# KDP.net
KiCad netlist of a schematic drawn in EasyEDA Pro
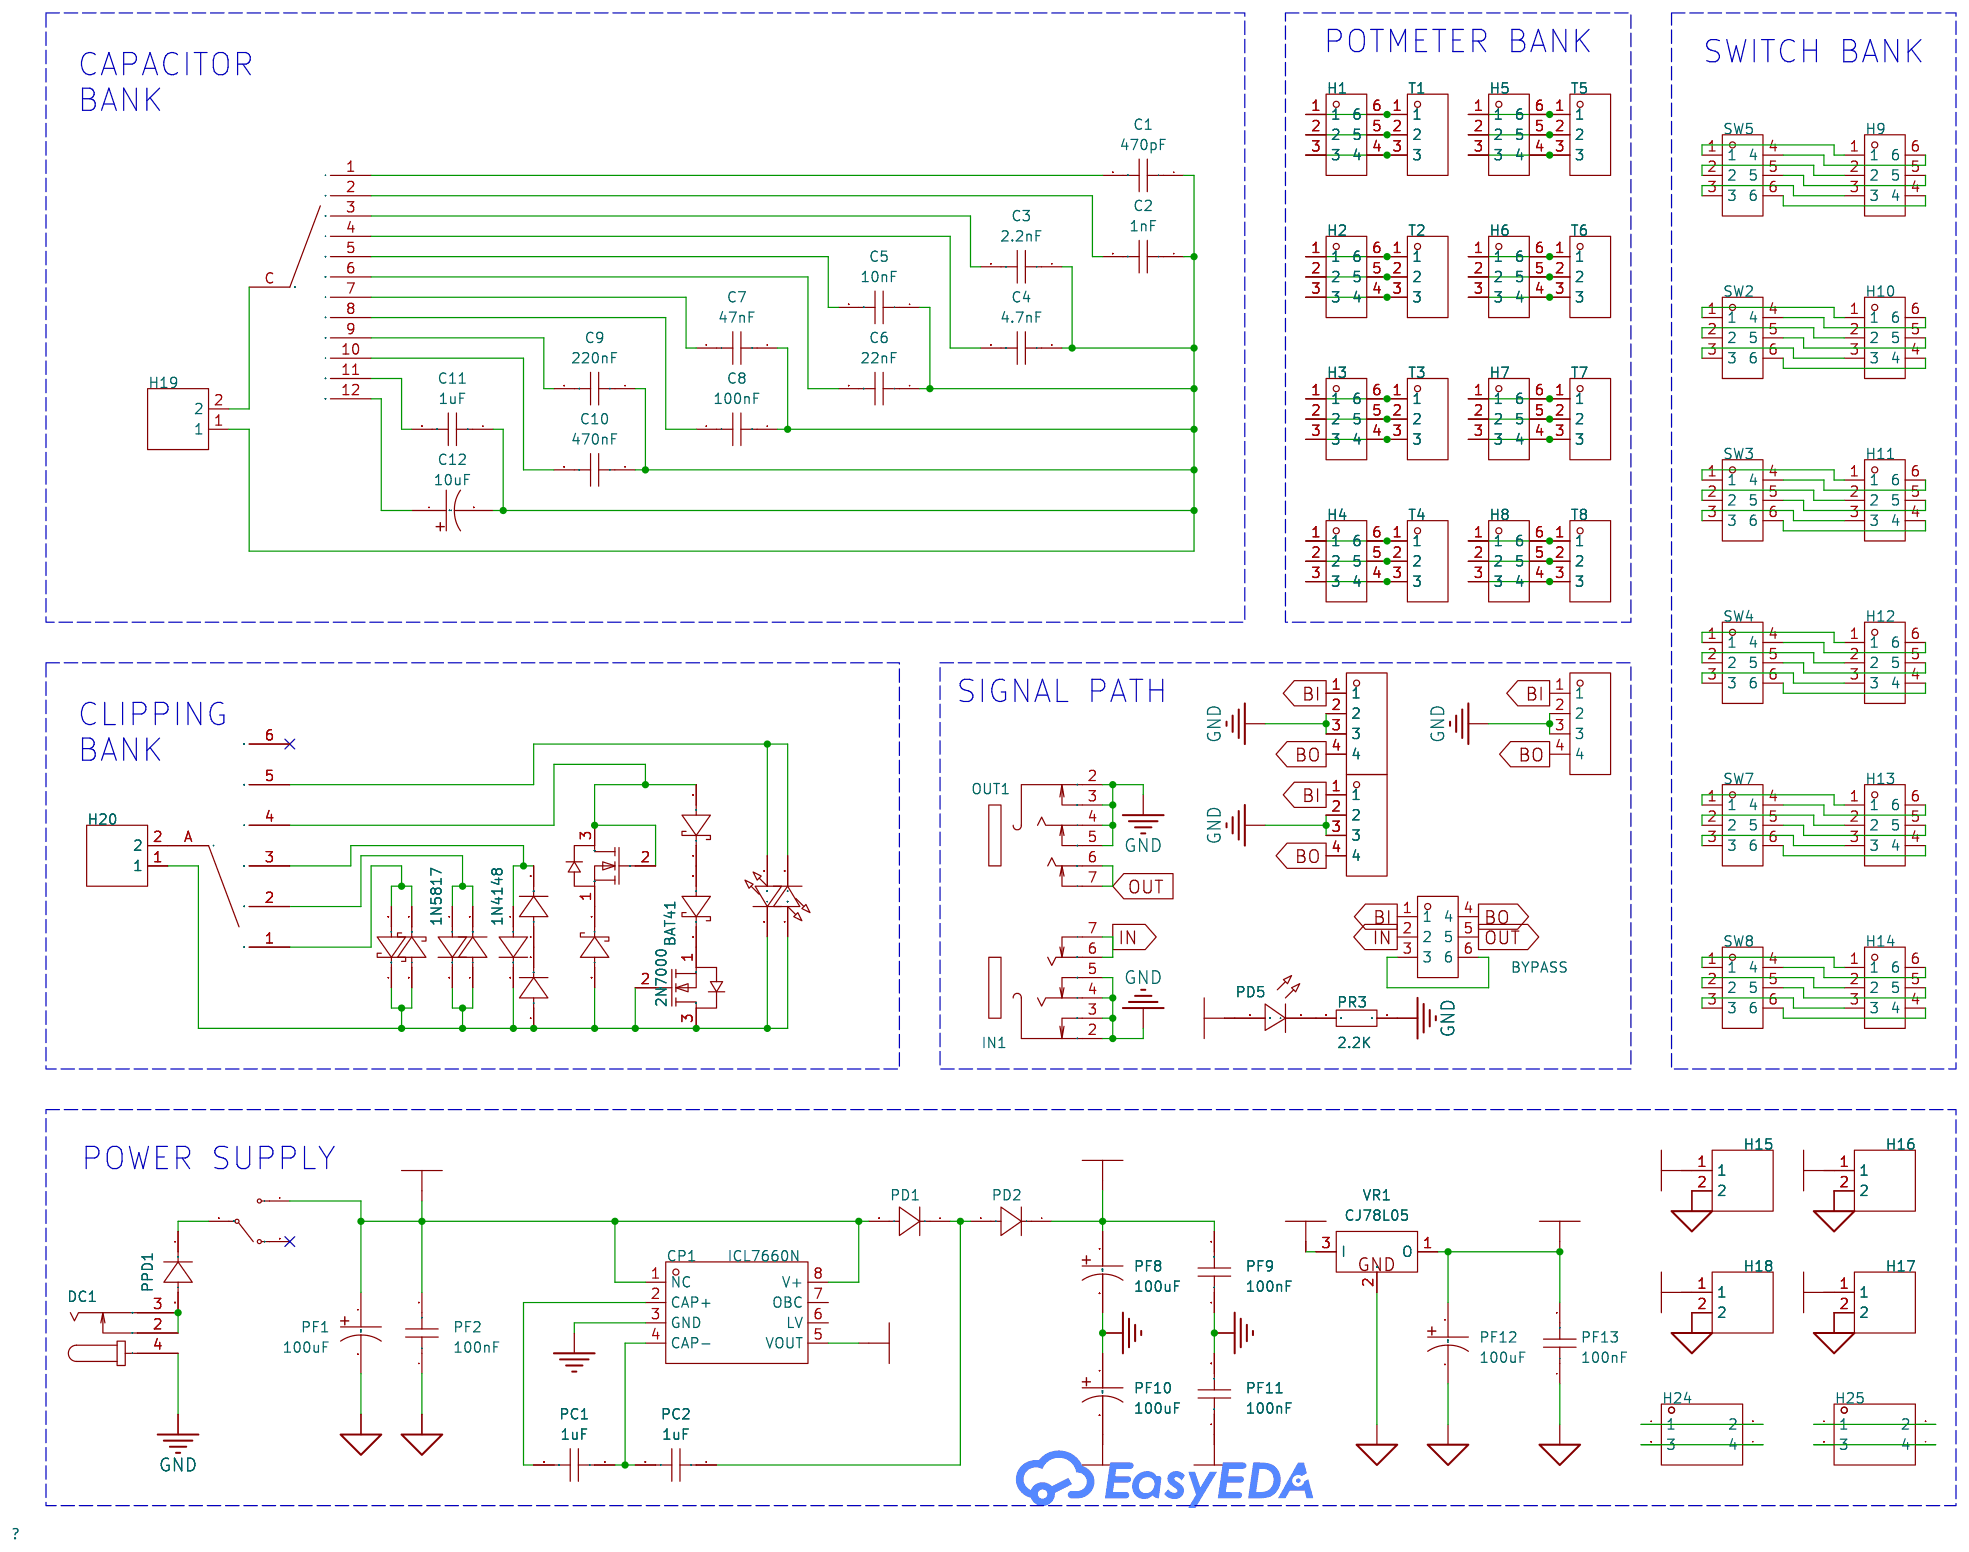
[diagram p0: schematic sheet]

(export (version "E")
  (design (tool "Eeschema 10.0.6"))
  (components
    (comp (ref "BYPASS")
      (value "ATTACK")
      (footprint "easyedapro:SW-TH_2MD1T1B1M1QES-5")
      (fields (field (name "Manufacturer") "Dailywell(德利威)"))
      (libsource (lib "easyedapro") (part "2MD1T1B1M1QES-5"))
    )
    (comp (ref "C1")
      (value "470pF")
      (fields
        (field (name "Manufacturer Part") "CC1H223ZC1FD3F4D1000")
        (field (name "Manufacturer") "Dersonic(德尔创)")
      )
      (libsource (lib "easyedapro") (part "CC1H223ZC1FD3F4D1000"))
    )
    (comp (ref "C2")
      (value "1nF")
      (fields
        (field (name "Manufacturer Part") "CC1H223ZC1FD3F4D1000")
        (field (name "Manufacturer") "Dersonic(德尔创)")
      )
      (libsource (lib "easyedapro") (part "CC1H223ZC1FD3F4D1000"))
    )
    (comp (ref "C3")
      (value "2.2nF")
      (fields
        (field (name "Manufacturer Part") "CC1H223ZC1FD3F4D1000")
        (field (name "Manufacturer") "Dersonic(德尔创)")
      )
      (libsource (lib "easyedapro") (part "CC1H223ZC1FD3F4D1000"))
    )
    (comp (ref "C4")
      (value "4.7nF")
      (fields
        (field (name "Manufacturer Part") "CC1H223ZC1FD3F4D1000")
        (field (name "Manufacturer") "Dersonic(德尔创)")
      )
      (libsource (lib "easyedapro") (part "CC1H223ZC1FD3F4D1000"))
    )
    (comp (ref "C5")
      (value "10nF")
      (fields
        (field (name "Manufacturer Part") "CC1H223ZC1FD3F4D1000")
        (field (name "Manufacturer") "Dersonic(德尔创)")
      )
      (libsource (lib "easyedapro") (part "CC1H223ZC1FD3F4D1000"))
    )
    (comp (ref "C6")
      (value "22nF")
      (fields
        (field (name "Manufacturer Part") "CC1H223ZC1FD3F4D1000")
        (field (name "Manufacturer") "Dersonic(德尔创)")
      )
      (libsource (lib "easyedapro") (part "CC1H223ZC1FD3F4D1000"))
    )
    (comp (ref "C7")
      (value "47nF")
      (fields
        (field (name "Manufacturer Part") "CC1H223ZC1FD3F4D1000")
        (field (name "Manufacturer") "Dersonic(德尔创)")
      )
      (libsource (lib "easyedapro") (part "CC1H223ZC1FD3F4D1000"))
    )
    (comp (ref "C8")
      (value "100nF")
      (fields
        (field (name "Manufacturer Part") "CC1H223ZC1FD3F4D1000")
        (field (name "Manufacturer") "Dersonic(德尔创)")
      )
      (libsource (lib "easyedapro") (part "CC1H223ZC1FD3F4D1000"))
    )
    (comp (ref "C9")
      (value "220nF")
      (fields
        (field (name "Manufacturer Part") "CC1H223ZC1FD3F4D1000")
        (field (name "Manufacturer") "Dersonic(德尔创)")
      )
      (libsource (lib "easyedapro") (part "CC1H223ZC1FD3F4D1000"))
    )
    (comp (ref "C10")
      (value "470nF")
      (fields
        (field (name "Manufacturer Part") "CC1H223ZC1FD3F4D1000")
        (field (name "Manufacturer") "Dersonic(德尔创)")
      )
      (libsource (lib "easyedapro") (part "CC1H223ZC1FD3F4D1000"))
    )
    (comp (ref "C11")
      (value "1uF")
      (fields
        (field (name "Manufacturer Part") "CC1H223ZC1FD3F4D1000")
        (field (name "Manufacturer") "Dersonic(德尔创)")
      )
      (libsource (lib "easyedapro") (part "CC1H223ZC1FD3F4D1000"))
    )
    (comp (ref "C12")
      (value "10uF")
      (footprint "easyedapro:CAP-TH_BD5.0-P2.00-D0.8-FD")
      (fields
        (field (name "Manufacturer Part") "25YXF47MFFC5X11")
        (field (name "Manufacturer") "rubycon(红宝石)")
      )
      (libsource (lib "easyedapro") (part "25YXF47MFFC5X11"))
    )
    (comp (ref "CP1")
      (value "ICL7660N")
      (footprint "easyedapro:DIP-8_L9.4-W6.4-P2.54-LS9.1-BL")
      (fields (field (name "Manufacturer") "HGSEMI(华冠)"))
      (libsource (lib "easyedapro") (part "ICL7660N"))
    )
    (comp (ref "C_SUB")
      (value "A30303RNCQ")
      (footprint "easyedapro:SW-TH_15P-BD26.2_A30303RNCQ")
      (fields (field (name "Manufacturer") "C&K"))
      (libsource (lib "easyedapro") (part "A30303_2_6"))
    )
    (comp (ref "D-SUB") (value "D-SUB") (libsource (lib "easyedapro") (part "A30303_2P6T")))
    (comp (ref "D1")
      (value "1N4148")
      (footprint "easyedapro:DO-35_BD2.2-L4.0-D0.50_1N4148")
      (fields (field (name "Manufacturer") "XCH(旭昌辉)"))
      (libsource (lib "easyedapro") (part "1N4148_C7437620"))
    )
    (comp (ref "D2")
      (value "1N4148")
      (footprint "easyedapro:DO-35_BD2.2-L4.0-D0.50_1N4148")
      (fields (field (name "Manufacturer") "XCH(旭昌辉)"))
      (libsource (lib "easyedapro") (part "1N4148_C7437620"))
    )
    (comp (ref "D3")
      (value "1N4148")
      (footprint "easyedapro:DO-35_BD2.2-L4.0-D0.50_1N4148")
      (fields (field (name "Manufacturer") "XCH(旭昌辉)"))
      (libsource (lib "easyedapro") (part "1N4148_C7437620"))
    )
    (comp (ref "D4")
      (value "1N4148")
      (footprint "easyedapro:DO-35_BD2.2-L4.0-D0.50_1N4148")
      (fields (field (name "Manufacturer") "XCH(旭昌辉)"))
      (libsource (lib "easyedapro") (part "1N4148_C7437620"))
    )
    (comp (ref "D5")
      (value "1N4148")
      (footprint "easyedapro:DO-35_BD2.2-L4.0-D0.50_1N4148")
      (fields (field (name "Manufacturer") "XCH(旭昌辉)"))
      (libsource (lib "easyedapro") (part "1N4148_C7437620"))
    )
    (comp (ref "D6")
      (value "BAT41")
      (footprint "easyedapro:DO-35_BD1.7-L3.8-P7.8-D0.5-FD")
      (fields (field (name "Manufacturer") "ST(意法半导体)"))
      (libsource (lib "easyedapro") (part "BAT41"))
    )
    (comp (ref "D7")
      (value "BAT41")
      (footprint "easyedapro:DO-35_BD1.7-L3.8-P7.8-D0.5-FD")
      (fields (field (name "Manufacturer") "ST(意法半导体)"))
      (libsource (lib "easyedapro") (part "BAT41"))
    )
    (comp (ref "D8")
      (value "BAT41")
      (footprint "easyedapro:DO-35_BD1.7-L3.8-P7.8-D0.5-FD")
      (fields (field (name "Manufacturer") "ST(意法半导体)"))
      (libsource (lib "easyedapro") (part "BAT41"))
    )
    (comp (ref "DC1")
      (value "HX DC005")
      (footprint "easyedapro:DC-IN-TH_HANXIA_HX-DC005-QT")
      (fields (field (name "Manufacturer") "hanxia(韩下)"))
      (libsource (lib "easyedapro") (part "HX DC005"))
    )
    (comp (ref "H1")
      (value "DS1001-01-06BT1NSF6X-JKB")
      (footprint "easyedapro:DIP-6_L7.6-W10.2-P2.54-LS7.6-BL")
      (fields (field (name "Manufacturer") "CONNFLY"))
      (libsource (lib "easyedapro") (part "DS1001-01-06BT1NSF6X-JKB"))
    )
    (comp (ref "H2")
      (value "DS1001-01-06BT1NSF6X-JKB")
      (footprint "easyedapro:DIP-6_L7.6-W10.2-P2.54-LS7.6-BL")
      (fields (field (name "Manufacturer") "CONNFLY"))
      (libsource (lib "easyedapro") (part "DS1001-01-06BT1NSF6X-JKB"))
    )
    (comp (ref "H3")
      (value "DS1001-01-06BT1NSF6X-JKB")
      (footprint "easyedapro:DIP-6_L7.6-W10.2-P2.54-LS7.6-BL")
      (fields (field (name "Manufacturer") "CONNFLY"))
      (libsource (lib "easyedapro") (part "DS1001-01-06BT1NSF6X-JKB"))
    )
    (comp (ref "H4")
      (value "DS1001-01-06BT1NSF6X-JKB")
      (footprint "easyedapro:DIP-6_L7.6-W10.2-P2.54-LS7.6-BL")
      (fields (field (name "Manufacturer") "CONNFLY"))
      (libsource (lib "easyedapro") (part "DS1001-01-06BT1NSF6X-JKB"))
    )
    (comp (ref "H5")
      (value "DS1001-01-06BT1NSF6X-JKB")
      (footprint "easyedapro:DIP-6_L7.6-W10.2-P2.54-LS7.6-BL")
      (fields (field (name "Manufacturer") "CONNFLY"))
      (libsource (lib "easyedapro") (part "DS1001-01-06BT1NSF6X-JKB"))
    )
    (comp (ref "H6")
      (value "DS1001-01-06BT1NSF6X-JKB")
      (footprint "easyedapro:DIP-6_L7.6-W10.2-P2.54-LS7.6-BL")
      (fields (field (name "Manufacturer") "CONNFLY"))
      (libsource (lib "easyedapro") (part "DS1001-01-06BT1NSF6X-JKB"))
    )
    (comp (ref "H7")
      (value "DS1001-01-06BT1NSF6X-JKB")
      (footprint "easyedapro:DIP-6_L7.6-W10.2-P2.54-LS7.6-BL")
      (fields (field (name "Manufacturer") "CONNFLY"))
      (libsource (lib "easyedapro") (part "DS1001-01-06BT1NSF6X-JKB"))
    )
    (comp (ref "H8")
      (value "DS1001-01-06BT1NSF6X-JKB")
      (footprint "easyedapro:DIP-6_L7.6-W10.2-P2.54-LS7.6-BL")
      (fields (field (name "Manufacturer") "CONNFLY"))
      (libsource (lib "easyedapro") (part "DS1001-01-06BT1NSF6X-JKB"))
    )
    (comp (ref "H9")
      (value "DS1001-01-06BT1NSF6X-JKB")
      (footprint "easyedapro:DIP-6_L7.6-W10.2-P2.54-LS7.6-BL")
      (fields (field (name "Manufacturer") "CONNFLY"))
      (libsource (lib "easyedapro") (part "DS1001-01-06BT1NSF6X-JKB"))
    )
    (comp (ref "H10")
      (value "DS1001-01-06BT1NSF6X-JKB")
      (footprint "easyedapro:DIP-6_L7.6-W10.2-P2.54-LS7.6-BL")
      (fields (field (name "Manufacturer") "CONNFLY"))
      (libsource (lib "easyedapro") (part "DS1001-01-06BT1NSF6X-JKB"))
    )
    (comp (ref "H11")
      (value "DS1001-01-06BT1NSF6X-JKB")
      (footprint "easyedapro:DIP-6_L7.6-W10.2-P2.54-LS7.6-BL")
      (fields (field (name "Manufacturer") "CONNFLY"))
      (libsource (lib "easyedapro") (part "DS1001-01-06BT1NSF6X-JKB"))
    )
    (comp (ref "H12")
      (value "DS1001-01-06BT1NSF6X-JKB")
      (footprint "easyedapro:DIP-6_L7.6-W10.2-P2.54-LS7.6-BL")
      (fields (field (name "Manufacturer") "CONNFLY"))
      (libsource (lib "easyedapro") (part "DS1001-01-06BT1NSF6X-JKB"))
    )
    (comp (ref "H13")
      (value "DS1001-01-06BT1NSF6X-JKB")
      (footprint "easyedapro:DIP-6_L7.6-W10.2-P2.54-LS7.6-BL")
      (fields (field (name "Manufacturer") "CONNFLY"))
      (libsource (lib "easyedapro") (part "DS1001-01-06BT1NSF6X-JKB"))
    )
    (comp (ref "H14")
      (value "DS1001-01-06BT1NSF6X-JKB")
      (footprint "easyedapro:DIP-6_L7.6-W10.2-P2.54-LS7.6-BL")
      (fields (field (name "Manufacturer") "CONNFLY"))
      (libsource (lib "easyedapro") (part "DS1001-01-06BT1NSF6X-JKB"))
    )
    (comp (ref "H15")
      (value "~")
      (footprint "easyedapro:HDR-TH_2P-P2.54-V-M-1")
      (libsource (lib "easyedapro") (part "210S-1*2P L=11.6MMGold-plated black"))
    )
    (comp (ref "H16")
      (value "~")
      (footprint "easyedapro:HDR-TH_2P-P2.54-V-M-1")
      (libsource (lib "easyedapro") (part "210S-1*2P L=11.6MMGold-plated black"))
    )
    (comp (ref "H17")
      (value "~")
      (footprint "easyedapro:HDR-TH_2P-P2.54-V-M-1")
      (libsource (lib "easyedapro") (part "210S-1*2P L=11.6MMGold-plated black"))
    )
    (comp (ref "H18")
      (value "~")
      (footprint "easyedapro:HDR-TH_2P-P2.54-V-M-1")
      (libsource (lib "easyedapro") (part "210S-1*2P L=11.6MMGold-plated black"))
    )
    (comp (ref "H19")
      (value "~")
      (footprint "easyedapro:HDR-TH_2P-P2.54-V-M-1")
      (libsource (lib "easyedapro") (part "210S-1*2P L=11.6MMGold-plated black"))
    )
    (comp (ref "H20")
      (value "~")
      (footprint "easyedapro:HDR-TH_2P-P2.54-V-M-1")
      (libsource (lib "easyedapro") (part "210S-1*2P L=11.6MMGold-plated black"))
    )
    (comp (ref "H21")
      (value "~")
      (footprint "easyedapro:HDR-TH_4P-P2.54-V-F")
      (libsource (lib "easyedapro") (part "2.54-1*4P母"))
    )
    (comp (ref "H22")
      (value "~")
      (footprint "easyedapro:HDR-TH_4P-P2.54-V-F")
      (libsource (lib "easyedapro") (part "2.54-1*4P母"))
    )
    (comp (ref "H23")
      (value "~")
      (footprint "easyedapro:HDR-TH_4P-P2.54-V-F")
      (libsource (lib "easyedapro") (part "2.54-1*4P母"))
    )
    (comp (ref "H24")
      (value "~")
      (footprint "easyedapro:HDR-TH_4P-P2.54-V-F-R2-C2-S2.54")
      (libsource (lib "easyedapro") (part "HDR-F-2.54_2x2"))
    )
    (comp (ref "H25")
      (value "~")
      (footprint "easyedapro:HDR-TH_4P-P2.54-V-F-R2-C2-S2.54")
      (libsource (lib "easyedapro") (part "HDR-F-2.54_2x2"))
    )
    (comp (ref "IN1")
      (value "INPUT")
      (footprint "easyedapro:AUDIO-TH_PJ-609BA")
      (fields (field (name "Manufacturer") "HOOYA(皓宇电子)"))
      (libsource (lib "easyedapro") (part "PJ-609BA"))
    )
    (comp (ref "OUT1")
      (value "OUTPUT")
      (footprint "easyedapro:AUDIO-TH_PJ-609BA")
      (fields (field (name "Manufacturer") "HOOYA(皓宇电子)"))
      (libsource (lib "easyedapro") (part "PJ-609BA"))
    )
    (comp (ref "PC1")
      (value "1uF")
      (fields
        (field (name "Manufacturer Part") "CC1H223ZC1FD3F4D1000")
        (field (name "Manufacturer") "Dersonic(德尔创)")
      )
      (libsource (lib "easyedapro") (part "CC1H223ZC1FD3F4D1000"))
    )
    (comp (ref "PC2")
      (value "1uF")
      (fields
        (field (name "Manufacturer Part") "CC1H223ZC1FD3F4D1000")
        (field (name "Manufacturer") "Dersonic(德尔创)")
      )
      (libsource (lib "easyedapro") (part "CC1H223ZC1FD3F4D1000"))
    )
    (comp (ref "PD1")
      (value "~")
      (footprint "easyedapro:DO-41_BD2.4-L4.7-P8.70-D0.9-RD")
      (libsource (lib "easyedapro") (part "D_1N4007"))
    )
    (comp (ref "PD2")
      (value "~")
      (footprint "easyedapro:DO-41_BD2.4-L4.7-P8.70-D0.9-RD")
      (libsource (lib "easyedapro") (part "D_1N4007"))
    )
    (comp (ref "PD5")
      (value "~")
      (footprint "easyedapro:LED-TH_BD3.0-P2.54-FD")
      (libsource (lib "easyedapro") (part "LED_TH-R"))
    )
    (comp (ref "PD6")
      (value "~")
      (footprint "easyedapro:LED-TH_BD3.0-P2.54-FD")
      (libsource (lib "easyedapro") (part "LED_TH-R"))
    )
    (comp (ref "PD7")
      (value "~")
      (footprint "easyedapro:LED-TH_BD3.0-P2.54-FD")
      (libsource (lib "easyedapro") (part "LED_TH-R"))
    )
    (comp (ref "PF1")
      (value "100uF")
      (footprint "easyedapro:CAP-TH_BD5.0-P2.00-D0.8-FD")
      (fields
        (field (name "Manufacturer Part") "25YXF47MFFC5X11")
        (field (name "Manufacturer") "rubycon(红宝石)")
      )
      (libsource (lib "easyedapro") (part "25YXF47MFFC5X11"))
    )
    (comp (ref "PF2")
      (value "100nF")
      (fields
        (field (name "Manufacturer Part") "CC1H223ZC1FD3F4D1000")
        (field (name "Manufacturer") "Dersonic(德尔创)")
      )
      (libsource (lib "easyedapro") (part "CC1H223ZC1FD3F4D1000"))
    )
    (comp (ref "PF8")
      (value "100uF")
      (footprint "easyedapro:CAP-TH_BD5.0-P2.00-D0.8-FD")
      (fields
        (field (name "Manufacturer Part") "25YXF47MFFC5X11")
        (field (name "Manufacturer") "rubycon(红宝石)")
      )
      (libsource (lib "easyedapro") (part "25YXF47MFFC5X11"))
    )
    (comp (ref "PF9")
      (value "100nF")
      (fields
        (field (name "Manufacturer Part") "CC1H223ZC1FD3F4D1000")
        (field (name "Manufacturer") "Dersonic(德尔创)")
      )
      (libsource (lib "easyedapro") (part "CC1H223ZC1FD3F4D1000"))
    )
    (comp (ref "PF10")
      (value "100uF")
      (footprint "easyedapro:CAP-TH_BD5.0-P2.00-D0.8-FD")
      (fields
        (field (name "Manufacturer Part") "25YXF47MFFC5X11")
        (field (name "Manufacturer") "rubycon(红宝石)")
      )
      (libsource (lib "easyedapro") (part "25YXF47MFFC5X11"))
    )
    (comp (ref "PF11")
      (value "100nF")
      (fields
        (field (name "Manufacturer Part") "CC1H223ZC1FD3F4D1000")
        (field (name "Manufacturer") "Dersonic(德尔创)")
      )
      (libsource (lib "easyedapro") (part "CC1H223ZC1FD3F4D1000"))
    )
    (comp (ref "PF12")
      (value "100uF")
      (footprint "easyedapro:CAP-TH_BD5.0-P2.00-D0.8-FD")
      (fields
        (field (name "Manufacturer Part") "25YXF47MFFC5X11")
        (field (name "Manufacturer") "rubycon(红宝石)")
      )
      (libsource (lib "easyedapro") (part "25YXF47MFFC5X11"))
    )
    (comp (ref "PF13")
      (value "100nF")
      (fields
        (field (name "Manufacturer Part") "CC1H223ZC1FD3F4D1000")
        (field (name "Manufacturer") "Dersonic(德尔创)")
      )
      (libsource (lib "easyedapro") (part "CC1H223ZC1FD3F4D1000"))
    )
    (comp (ref "POWER")
      (value "2MS1T1B1M2QES-5")
      (footprint "easyedapro:SW-TH_2MS1T1B1M2QES-5")
      (fields (field (name "Manufacturer") "Dailywell(德利威)"))
      (libsource (lib "easyedapro") (part "2MS1T1B1M2QES-5"))
    )
    (comp (ref "PPD1")
      (value "~")
      (footprint "easyedapro:DO-41_BD2.4-L4.7-P8.70-D0.9-RD")
      (libsource (lib "easyedapro") (part "D_1N4007"))
    )
    (comp (ref "PR3")
      (value "2.2K")
      (footprint "easyedapro:R_AXIAL-0.4")
      (libsource (lib "easyedapro") (part "Res"))
    )
    (comp (ref "Q1")
      (value "2N7000")
      (footprint "easyedapro:TO-92-3_L4.9-W3.7-P1.27-L")
      (fields (field (name "Manufacturer") "onsemi(安森美)"))
      (libsource (lib "easyedapro") (part "2N7000_C232838"))
    )
    (comp (ref "Q2")
      (value "2N7000")
      (footprint "easyedapro:TO-92-3_L4.9-W3.7-P1.27-L")
      (fields (field (name "Manufacturer") "onsemi(安森美)"))
      (libsource (lib "easyedapro") (part "2N7000_C232838"))
    )
    (comp (ref "SW2")
      (value "ATTACK")
      (footprint "easyedapro:SW-TH_2MD1T1B1M1QES-5")
      (fields (field (name "Manufacturer") "Dailywell(德利威)"))
      (libsource (lib "easyedapro") (part "2MD1T1B1M1QES-5"))
    )
    (comp (ref "SW3")
      (value "ATTACK")
      (footprint "easyedapro:SW-TH_2MD1T1B1M1QES-5")
      (fields (field (name "Manufacturer") "Dailywell(德利威)"))
      (libsource (lib "easyedapro") (part "2MD1T1B1M1QES-5"))
    )
    (comp (ref "SW4")
      (value "ATTACK")
      (footprint "easyedapro:SW-TH_2MD1T1B1M1QES-5")
      (fields (field (name "Manufacturer") "Dailywell(德利威)"))
      (libsource (lib "easyedapro") (part "2MD1T1B1M1QES-5"))
    )
    (comp (ref "SW5")
      (value "ATTACK")
      (footprint "easyedapro:SW-TH_2MD1T1B1M1QES-5")
      (fields (field (name "Manufacturer") "Dailywell(德利威)"))
      (libsource (lib "easyedapro") (part "2MD1T1B1M1QES-5"))
    )
    (comp (ref "SW7")
      (value "ATTACK")
      (footprint "easyedapro:SW-TH_2MD1T1B1M1QES-5")
      (fields (field (name "Manufacturer") "Dailywell(德利威)"))
      (libsource (lib "easyedapro") (part "2MD1T1B1M1QES-5"))
    )
    (comp (ref "SW8")
      (value "ATTACK")
      (footprint "easyedapro:SW-TH_2MD1T1B1M1QES-5")
      (fields (field (name "Manufacturer") "Dailywell(德利威)"))
      (libsource (lib "easyedapro") (part "2MD1T1B1M1QES-5"))
    )
    (comp (ref "T1")
      (value "DG103-5.0-03P-14-00A(H)")
      (footprint "easyedapro:CONN-TH_DG103-5.0-03P-14-00A")
      (fields (field (name "Manufacturer") "DEGSON(高正/高松)"))
      (libsource (lib "easyedapro") (part "DG103-5.0-03P-14-00A(H)"))
    )
    (comp (ref "T2")
      (value "DG103-5.0-03P-14-00A(H)")
      (footprint "easyedapro:CONN-TH_DG103-5.0-03P-14-00A")
      (fields (field (name "Manufacturer") "DEGSON(高正/高松)"))
      (libsource (lib "easyedapro") (part "DG103-5.0-03P-14-00A(H)"))
    )
    (comp (ref "T3")
      (value "DG103-5.0-03P-14-00A(H)")
      (footprint "easyedapro:CONN-TH_DG103-5.0-03P-14-00A")
      (fields (field (name "Manufacturer") "DEGSON(高正/高松)"))
      (libsource (lib "easyedapro") (part "DG103-5.0-03P-14-00A(H)"))
    )
    (comp (ref "T4")
      (value "DG103-5.0-03P-14-00A(H)")
      (footprint "easyedapro:CONN-TH_DG103-5.0-03P-14-00A")
      (fields (field (name "Manufacturer") "DEGSON(高正/高松)"))
      (libsource (lib "easyedapro") (part "DG103-5.0-03P-14-00A(H)"))
    )
    (comp (ref "T5")
      (value "DG103-5.0-03P-14-00A(H)")
      (footprint "easyedapro:CONN-TH_DG103-5.0-03P-14-00A")
      (fields (field (name "Manufacturer") "DEGSON(高正/高松)"))
      (libsource (lib "easyedapro") (part "DG103-5.0-03P-14-00A(H)"))
    )
    (comp (ref "T6")
      (value "DG103-5.0-03P-14-00A(H)")
      (footprint "easyedapro:CONN-TH_DG103-5.0-03P-14-00A")
      (fields (field (name "Manufacturer") "DEGSON(高正/高松)"))
      (libsource (lib "easyedapro") (part "DG103-5.0-03P-14-00A(H)"))
    )
    (comp (ref "T7")
      (value "DG103-5.0-03P-14-00A(H)")
      (footprint "easyedapro:CONN-TH_DG103-5.0-03P-14-00A")
      (fields (field (name "Manufacturer") "DEGSON(高正/高松)"))
      (libsource (lib "easyedapro") (part "DG103-5.0-03P-14-00A(H)"))
    )
    (comp (ref "T8")
      (value "DG103-5.0-03P-14-00A(H)")
      (footprint "easyedapro:CONN-TH_DG103-5.0-03P-14-00A")
      (fields (field (name "Manufacturer") "DEGSON(高正/高松)"))
      (libsource (lib "easyedapro") (part "DG103-5.0-03P-14-00A(H)"))
    )
    (comp (ref "U2")
      (value "1N5817")
      (footprint "easyedapro:DO-41_BD2.4-L4.7-P8.70-D0.8-RD")
      (fields (field (name "Manufacturer") "ST(意法半导体)"))
      (libsource (lib "easyedapro") (part "1N5817_C2935162"))
    )
    (comp (ref "U3")
      (value "1N5817")
      (footprint "easyedapro:DO-41_BD2.4-L4.7-P8.70-D0.8-RD")
      (fields (field (name "Manufacturer") "ST(意法半导体)"))
      (libsource (lib "easyedapro") (part "1N5817_C2935162"))
    )
    (comp (ref "VR1")
      (value "CJ78L05")
      (footprint "easyedapro:TO-92-3_L4.9-W3.7-P1.27-L")
      (fields (field (name "Manufacturer") "CJ(江苏长电/长晶)"))
      (libsource (lib "easyedapro") (part "CJ78L05 5V TO-92"))
    )
  )
  (nets
    (net (code "1") (name "+9V") (class "Default")
      (node (ref "CP1") (pin "1") (pinfunction "NC_1") (pintype "unspecified"))
      (node (ref "CP1") (pin "8") (pinfunction "V+_8") (pintype "unspecified"))
      (node (ref "H16") (pin "1") (pinfunction "1_1") (pintype "unspecified"))
      (node (ref "PD1") (pin "2") (pinfunction "A_2") (pintype "input"))
      (node (ref "PD5") (pin "1") (pinfunction "C_1") (pintype "input"))
      (node (ref "PF1") (pin "1") (pinfunction "1_1") (pintype "input"))
      (node (ref "PF2") (pin "2") (pinfunction "2_2") (pintype "input"))
      (node (ref "POWER") (pin "1") (pinfunction "1_1") (pintype "unspecified"))
      (node (ref "VR1") (pin "3") (pinfunction "I_3") (pintype "unspecified"))
    )
    (net (code "2") (name "+18V") (class "Default")
      (node (ref "H15") (pin "1") (pinfunction "1_1") (pintype "unspecified"))
      (node (ref "PD2") (pin "1") (pinfunction "K_1") (pintype "input"))
      (node (ref "PF8") (pin "1") (pinfunction "1_1") (pintype "input"))
      (node (ref "PF9") (pin "2") (pinfunction "2_2") (pintype "input"))
    )
    (net (code "3") (name "-9V") (class "Default")
      (node (ref "CP1") (pin "5") (pinfunction "VOUT_5") (pintype "unspecified"))
      (node (ref "H17") (pin "1") (pinfunction "1_1") (pintype "unspecified"))
      (node (ref "PF10") (pin "2") (pinfunction "2_2") (pintype "input"))
      (node (ref "PF11") (pin "1") (pinfunction "1_1") (pintype "input"))
    )
    (net (code "4") (name "5V") (class "Default")
      (node (ref "H18") (pin "1") (pinfunction "1_1") (pintype "unspecified"))
      (node (ref "PF12") (pin "1") (pinfunction "1_1") (pintype "input"))
      (node (ref "PF13") (pin "2") (pinfunction "2_2") (pintype "input"))
      (node (ref "VR1") (pin "1") (pinfunction "O_1") (pintype "unspecified"))
    )
    (net (code "5") (name "BI") (class "Default")
      (node (ref "BYPASS") (pin "1") (pinfunction "1_1") (pintype "unspecified"))
      (node (ref "H21") (pin "1") (pinfunction "1_1") (pintype "input"))
      (node (ref "H22") (pin "1") (pinfunction "1_1") (pintype "input"))
      (node (ref "H23") (pin "1") (pinfunction "1_1") (pintype "input"))
    )
    (net (code "6") (name "BO") (class "Default")
      (node (ref "BYPASS") (pin "4") (pinfunction "4_4") (pintype "unspecified"))
      (node (ref "H21") (pin "4") (pinfunction "4_4") (pintype "input"))
      (node (ref "H22") (pin "4") (pinfunction "4_4") (pintype "input"))
      (node (ref "H23") (pin "4") (pinfunction "4_4") (pintype "input"))
    )
    (net (code "7") (name "GND") (class "Default")
      (node (ref "DC1") (pin "4") (pinfunction "4_4") (pintype "input"))
      (node (ref "H21") (pin "2") (pinfunction "2_2") (pintype "input"))
      (node (ref "H21") (pin "3") (pinfunction "3_3") (pintype "input"))
      (node (ref "H22") (pin "2") (pinfunction "2_2") (pintype "input"))
      (node (ref "H22") (pin "3") (pinfunction "3_3") (pintype "input"))
      (node (ref "H23") (pin "2") (pinfunction "2_2") (pintype "input"))
      (node (ref "H23") (pin "3") (pinfunction "3_3") (pintype "input"))
      (node (ref "IN1") (pin "2") (pinfunction "2_2") (pintype "input"))
      (node (ref "IN1") (pin "3") (pinfunction "3_3") (pintype "input"))
      (node (ref "IN1") (pin "4") (pinfunction "4_4") (pintype "input"))
      (node (ref "IN1") (pin "5") (pinfunction "5_5") (pintype "input"))
      (node (ref "OUT1") (pin "2") (pinfunction "2_2") (pintype "input"))
      (node (ref "OUT1") (pin "3") (pinfunction "3_3") (pintype "input"))
      (node (ref "OUT1") (pin "4") (pinfunction "4_4") (pintype "input"))
      (node (ref "OUT1") (pin "5") (pinfunction "5_5") (pintype "input"))
      (node (ref "PR3") (pin "1") (pinfunction "1_1") (pintype "input"))
    )
    (net (code "8") (name "IN") (class "Default")
      (node (ref "BYPASS") (pin "2") (pinfunction "2_2") (pintype "unspecified"))
      (node (ref "IN1") (pin "6") (pinfunction "6_6") (pintype "input"))
      (node (ref "IN1") (pin "7") (pinfunction "7_7") (pintype "input"))
    )
    (net (code "9") (name "Net-(BYPASS-Pad3)") (class "Default")
      (node (ref "BYPASS") (pin "3") (pinfunction "3_3") (pintype "unspecified"))
      (node (ref "BYPASS") (pin "6") (pinfunction "6_6") (pintype "unspecified"))
    )
    (net (code "10") (name "Net-(C1-Pad1)") (class "Default")
      (node (ref "C1") (pin "1") (pinfunction "1_1") (pintype "input"))
      (node (ref "C10") (pin "1") (pinfunction "1_1") (pintype "input"))
      (node (ref "C11") (pin "1") (pinfunction "1_1") (pintype "input"))
      (node (ref "C12") (pin "2") (pinfunction "2_2") (pintype "input"))
      (node (ref "C2") (pin "1") (pinfunction "1_1") (pintype "input"))
      (node (ref "C3") (pin "1") (pinfunction "1_1") (pintype "input"))
      (node (ref "C4") (pin "1") (pinfunction "1_1") (pintype "input"))
      (node (ref "C5") (pin "1") (pinfunction "1_1") (pintype "input"))
      (node (ref "C6") (pin "1") (pinfunction "1_1") (pintype "input"))
      (node (ref "C7") (pin "1") (pinfunction "1_1") (pintype "input"))
      (node (ref "C8") (pin "1") (pinfunction "1_1") (pintype "input"))
      (node (ref "C9") (pin "1") (pinfunction "1_1") (pintype "input"))
      (node (ref "H19") (pin "1") (pinfunction "1_1") (pintype "unspecified"))
    )
    (net (code "11") (name "Net-(C1-Pad2)") (class "Default")
      (node (ref "C1") (pin "2") (pinfunction "2_2") (pintype "input"))
      (node (ref "C_SUB") (pin "1") (pinfunction "1_1") (pintype "unspecified"))
    )
    (net (code "12") (name "Net-(C2-Pad2)") (class "Default")
      (node (ref "C2") (pin "2") (pinfunction "2_2") (pintype "input"))
      (node (ref "C_SUB") (pin "2") (pinfunction "2_2") (pintype "unspecified"))
    )
    (net (code "13") (name "Net-(C3-Pad2)") (class "Default")
      (node (ref "C3") (pin "2") (pinfunction "2_2") (pintype "input"))
      (node (ref "C_SUB") (pin "3") (pinfunction "3_3") (pintype "unspecified"))
    )
    (net (code "14") (name "Net-(C4-Pad2)") (class "Default")
      (node (ref "C4") (pin "2") (pinfunction "2_2") (pintype "input"))
      (node (ref "C_SUB") (pin "4") (pinfunction "4_4") (pintype "unspecified"))
    )
    (net (code "15") (name "Net-(C5-Pad2)") (class "Default")
      (node (ref "C5") (pin "2") (pinfunction "2_2") (pintype "input"))
      (node (ref "C_SUB") (pin "5") (pinfunction "5_5") (pintype "unspecified"))
    )
    (net (code "16") (name "Net-(C6-Pad2)") (class "Default")
      (node (ref "C6") (pin "2") (pinfunction "2_2") (pintype "input"))
      (node (ref "C_SUB") (pin "6") (pinfunction "6_6") (pintype "unspecified"))
    )
    (net (code "17") (name "Net-(C7-Pad2)") (class "Default")
      (node (ref "C7") (pin "2") (pinfunction "2_2") (pintype "input"))
      (node (ref "C_SUB") (pin "7") (pinfunction "1_7") (pintype "unspecified"))
    )
    (net (code "18") (name "Net-(C8-Pad2)") (class "Default")
      (node (ref "C8") (pin "2") (pinfunction "2_2") (pintype "input"))
      (node (ref "C_SUB") (pin "8") (pinfunction "2_8") (pintype "unspecified"))
    )
    (net (code "19") (name "Net-(C9-Pad2)") (class "Default")
      (node (ref "C9") (pin "2") (pinfunction "2_2") (pintype "input"))
      (node (ref "C_SUB") (pin "9") (pinfunction "3_9") (pintype "unspecified"))
    )
    (net (code "20") (name "Net-(C10-Pad2)") (class "Default")
      (node (ref "C10") (pin "2") (pinfunction "2_2") (pintype "input"))
      (node (ref "C_SUB") (pin "10") (pinfunction "4_10") (pintype "unspecified"))
    )
    (net (code "21") (name "Net-(C11-Pad2)") (class "Default")
      (node (ref "C11") (pin "2") (pinfunction "2_2") (pintype "input"))
      (node (ref "C_SUB") (pin "11") (pinfunction "5_11") (pintype "unspecified"))
    )
    (net (code "22") (name "Net-(C12-Pad1)") (class "Default")
      (node (ref "C12") (pin "1") (pinfunction "1_1") (pintype "input"))
      (node (ref "C_SUB") (pin "12") (pinfunction "6_12") (pintype "unspecified"))
    )
    (net (code "23") (name "Net-(CP1-CAP+)") (class "Default")
      (node (ref "CP1") (pin "2") (pinfunction "CAP+_2") (pintype "unspecified"))
      (node (ref "PC1") (pin "2") (pinfunction "2_2") (pintype "input"))
    )
    (net (code "24") (name "Net-(CP1-CAP-)") (class "Default")
      (node (ref "CP1") (pin "4") (pinfunction "CAP-_4") (pintype "unspecified"))
      (node (ref "PC1") (pin "1") (pinfunction "1_1") (pintype "input"))
      (node (ref "PC2") (pin "2") (pinfunction "2_2") (pintype "input"))
    )
    (net (code "25") (name "Net-(C_SUB-PadC)") (class "Default")
      (node (ref "C_SUB") (pin "C") (pinfunction "C_C") (pintype "unspecified"))
      (node (ref "H19") (pin "2") (pinfunction "2_2") (pintype "unspecified"))
    )
    (net (code "26") (name "Net-(D-SUB-PadA)") (class "Default")
      (node (ref "D-SUB") (pin "A") (pinfunction "A_A") (pintype "unspecified"))
      (node (ref "H20") (pin "2") (pinfunction "2_2") (pintype "unspecified"))
    )
    (net (code "27") (name "Net-(D1-A)") (class "Default")
      (node (ref "D-SUB") (pin "2") (pinfunction "2_2") (pintype "unspecified"))
      (node (ref "D1") (pin "1") (pinfunction "A_1") (pintype "unspecified"))
      (node (ref "D2") (pin "2") (pinfunction "C_2") (pintype "unspecified"))
    )
    (net (code "28") (name "Net-(D1-C)") (class "Default")
      (node (ref "D1") (pin "2") (pinfunction "C_2") (pintype "unspecified"))
      (node (ref "D2") (pin "1") (pinfunction "A_1") (pintype "unspecified"))
      (node (ref "D3") (pin "2") (pinfunction "C_2") (pintype "unspecified"))
      (node (ref "D5") (pin "1") (pinfunction "A_1") (pintype "unspecified"))
      (node (ref "D6") (pin "2") (pinfunction "A_2") (pintype "unspecified"))
      (node (ref "H20") (pin "1") (pinfunction "1_1") (pintype "unspecified"))
      (node (ref "PD6") (pin "1") (pinfunction "C_1") (pintype "input"))
      (node (ref "PD7") (pin "2") (pinfunction "A_2") (pintype "input"))
      (node (ref "Q1") (pin "2") (pinfunction "G_2") (pintype "unspecified"))
      (node (ref "Q1") (pin "3") (pinfunction "D_3") (pintype "unspecified"))
      (node (ref "U2") (pin "1") (pinfunction "C_1") (pintype "unspecified"))
      (node (ref "U3") (pin "2") (pinfunction "A_2") (pintype "unspecified"))
    )
    (net (code "29") (name "Net-(D3-A)") (class "Default")
      (node (ref "D-SUB") (pin "3") (pinfunction "3_3") (pintype "unspecified"))
      (node (ref "D3") (pin "1") (pinfunction "A_1") (pintype "unspecified"))
      (node (ref "D4") (pin "2") (pinfunction "C_2") (pintype "unspecified"))
    )
    (net (code "30") (name "Net-(D4-A)") (class "Default")
      (node (ref "D4") (pin "1") (pinfunction "A_1") (pintype "unspecified"))
      (node (ref "D5") (pin "2") (pinfunction "C_2") (pintype "unspecified"))
    )
    (net (code "31") (name "Net-(D6-K)") (class "Default")
      (node (ref "D6") (pin "1") (pinfunction "K_1") (pintype "unspecified"))
      (node (ref "Q2") (pin "1") (pinfunction "S_1") (pintype "unspecified"))
    )
    (net (code "32") (name "Net-(D7-A)") (class "Default")
      (node (ref "D7") (pin "2") (pinfunction "A_2") (pintype "unspecified"))
      (node (ref "D8") (pin "1") (pinfunction "K_1") (pintype "unspecified"))
    )
    (net (code "33") (name "Net-(D7-K)") (class "Default")
      (node (ref "D7") (pin "1") (pinfunction "K_1") (pintype "unspecified"))
      (node (ref "Q1") (pin "1") (pinfunction "S_1") (pintype "unspecified"))
    )
    (net (code "34") (name "Net-(D8-A)") (class "Default")
      (node (ref "D-SUB") (pin "4") (pinfunction "4_4") (pintype "unspecified"))
      (node (ref "D8") (pin "2") (pinfunction "A_2") (pintype "unspecified"))
      (node (ref "Q2") (pin "2") (pinfunction "G_2") (pintype "unspecified"))
      (node (ref "Q2") (pin "3") (pinfunction "D_3") (pintype "unspecified"))
    )
    (net (code "35") (name "Net-(H1-Pad1)") (class "Default")
      (node (ref "H1") (pin "1") (pinfunction "1_1") (pintype "unspecified"))
      (node (ref "H1") (pin "6") (pinfunction "6_6") (pintype "unspecified"))
      (node (ref "T1") (pin "1") (pinfunction "1_1") (pintype "unspecified"))
    )
    (net (code "36") (name "Net-(H1-Pad2)") (class "Default")
      (node (ref "H1") (pin "2") (pinfunction "2_2") (pintype "unspecified"))
      (node (ref "H1") (pin "5") (pinfunction "5_5") (pintype "unspecified"))
      (node (ref "T1") (pin "2") (pinfunction "2_2") (pintype "unspecified"))
    )
    (net (code "37") (name "Net-(H1-Pad3)") (class "Default")
      (node (ref "H1") (pin "3") (pinfunction "3_3") (pintype "unspecified"))
      (node (ref "H1") (pin "4") (pinfunction "4_4") (pintype "unspecified"))
      (node (ref "T1") (pin "3") (pinfunction "3_3") (pintype "unspecified"))
    )
    (net (code "38") (name "Net-(H2-Pad1)") (class "Default")
      (node (ref "H2") (pin "1") (pinfunction "1_1") (pintype "unspecified"))
      (node (ref "H2") (pin "6") (pinfunction "6_6") (pintype "unspecified"))
      (node (ref "T2") (pin "1") (pinfunction "1_1") (pintype "unspecified"))
    )
    (net (code "39") (name "Net-(H2-Pad2)") (class "Default")
      (node (ref "H2") (pin "2") (pinfunction "2_2") (pintype "unspecified"))
      (node (ref "H2") (pin "5") (pinfunction "5_5") (pintype "unspecified"))
      (node (ref "T2") (pin "2") (pinfunction "2_2") (pintype "unspecified"))
    )
    (net (code "40") (name "Net-(H2-Pad3)") (class "Default")
      (node (ref "H2") (pin "3") (pinfunction "3_3") (pintype "unspecified"))
      (node (ref "H2") (pin "4") (pinfunction "4_4") (pintype "unspecified"))
      (node (ref "T2") (pin "3") (pinfunction "3_3") (pintype "unspecified"))
    )
    (net (code "41") (name "Net-(H3-Pad1)") (class "Default")
      (node (ref "H3") (pin "1") (pinfunction "1_1") (pintype "unspecified"))
      (node (ref "H3") (pin "6") (pinfunction "6_6") (pintype "unspecified"))
      (node (ref "T3") (pin "1") (pinfunction "1_1") (pintype "unspecified"))
    )
    (net (code "42") (name "Net-(H3-Pad2)") (class "Default")
      (node (ref "H3") (pin "2") (pinfunction "2_2") (pintype "unspecified"))
      (node (ref "H3") (pin "5") (pinfunction "5_5") (pintype "unspecified"))
      (node (ref "T3") (pin "2") (pinfunction "2_2") (pintype "unspecified"))
    )
    (net (code "43") (name "Net-(H3-Pad3)") (class "Default")
      (node (ref "H3") (pin "3") (pinfunction "3_3") (pintype "unspecified"))
      (node (ref "H3") (pin "4") (pinfunction "4_4") (pintype "unspecified"))
      (node (ref "T3") (pin "3") (pinfunction "3_3") (pintype "unspecified"))
    )
    (net (code "44") (name "Net-(H4-Pad1)") (class "Default")
      (node (ref "H4") (pin "1") (pinfunction "1_1") (pintype "unspecified"))
      (node (ref "H4") (pin "6") (pinfunction "6_6") (pintype "unspecified"))
      (node (ref "T4") (pin "1") (pinfunction "1_1") (pintype "unspecified"))
    )
    (net (code "45") (name "Net-(H4-Pad2)") (class "Default")
      (node (ref "H4") (pin "2") (pinfunction "2_2") (pintype "unspecified"))
      (node (ref "H4") (pin "5") (pinfunction "5_5") (pintype "unspecified"))
      (node (ref "T4") (pin "2") (pinfunction "2_2") (pintype "unspecified"))
    )
    (net (code "46") (name "Net-(H4-Pad3)") (class "Default")
      (node (ref "H4") (pin "3") (pinfunction "3_3") (pintype "unspecified"))
      (node (ref "H4") (pin "4") (pinfunction "4_4") (pintype "unspecified"))
      (node (ref "T4") (pin "3") (pinfunction "3_3") (pintype "unspecified"))
    )
    (net (code "47") (name "Net-(H5-Pad1)") (class "Default")
      (node (ref "H5") (pin "1") (pinfunction "1_1") (pintype "unspecified"))
      (node (ref "H5") (pin "6") (pinfunction "6_6") (pintype "unspecified"))
      (node (ref "T5") (pin "1") (pinfunction "1_1") (pintype "unspecified"))
    )
    (net (code "48") (name "Net-(H5-Pad2)") (class "Default")
      (node (ref "H5") (pin "2") (pinfunction "2_2") (pintype "unspecified"))
      (node (ref "H5") (pin "5") (pinfunction "5_5") (pintype "unspecified"))
      (node (ref "T5") (pin "2") (pinfunction "2_2") (pintype "unspecified"))
    )
    (net (code "49") (name "Net-(H5-Pad3)") (class "Default")
      (node (ref "H5") (pin "3") (pinfunction "3_3") (pintype "unspecified"))
      (node (ref "H5") (pin "4") (pinfunction "4_4") (pintype "unspecified"))
      (node (ref "T5") (pin "3") (pinfunction "3_3") (pintype "unspecified"))
    )
    (net (code "50") (name "Net-(H6-Pad1)") (class "Default")
      (node (ref "H6") (pin "1") (pinfunction "1_1") (pintype "unspecified"))
      (node (ref "H6") (pin "6") (pinfunction "6_6") (pintype "unspecified"))
      (node (ref "T6") (pin "1") (pinfunction "1_1") (pintype "unspecified"))
    )
    (net (code "51") (name "Net-(H6-Pad2)") (class "Default")
      (node (ref "H6") (pin "2") (pinfunction "2_2") (pintype "unspecified"))
      (node (ref "H6") (pin "5") (pinfunction "5_5") (pintype "unspecified"))
      (node (ref "T6") (pin "2") (pinfunction "2_2") (pintype "unspecified"))
    )
    (net (code "52") (name "Net-(H6-Pad3)") (class "Default")
      (node (ref "H6") (pin "3") (pinfunction "3_3") (pintype "unspecified"))
      (node (ref "H6") (pin "4") (pinfunction "4_4") (pintype "unspecified"))
      (node (ref "T6") (pin "3") (pinfunction "3_3") (pintype "unspecified"))
    )
    (net (code "53") (name "Net-(H7-Pad1)") (class "Default")
      (node (ref "H7") (pin "1") (pinfunction "1_1") (pintype "unspecified"))
      (node (ref "H7") (pin "6") (pinfunction "6_6") (pintype "unspecified"))
      (node (ref "T7") (pin "1") (pinfunction "1_1") (pintype "unspecified"))
    )
    (net (code "54") (name "Net-(H7-Pad2)") (class "Default")
      (node (ref "H7") (pin "2") (pinfunction "2_2") (pintype "unspecified"))
      (node (ref "H7") (pin "5") (pinfunction "5_5") (pintype "unspecified"))
      (node (ref "T7") (pin "2") (pinfunction "2_2") (pintype "unspecified"))
    )
    (net (code "55") (name "Net-(H7-Pad3)") (class "Default")
      (node (ref "H7") (pin "3") (pinfunction "3_3") (pintype "unspecified"))
      (node (ref "H7") (pin "4") (pinfunction "4_4") (pintype "unspecified"))
      (node (ref "T7") (pin "3") (pinfunction "3_3") (pintype "unspecified"))
    )
    (net (code "56") (name "Net-(H8-Pad1)") (class "Default")
      (node (ref "H8") (pin "1") (pinfunction "1_1") (pintype "unspecified"))
      (node (ref "H8") (pin "6") (pinfunction "6_6") (pintype "unspecified"))
      (node (ref "T8") (pin "1") (pinfunction "1_1") (pintype "unspecified"))
    )
    (net (code "57") (name "Net-(H8-Pad2)") (class "Default")
      (node (ref "H8") (pin "2") (pinfunction "2_2") (pintype "unspecified"))
      (node (ref "H8") (pin "5") (pinfunction "5_5") (pintype "unspecified"))
      (node (ref "T8") (pin "2") (pinfunction "2_2") (pintype "unspecified"))
    )
    (net (code "58") (name "Net-(H8-Pad3)") (class "Default")
      (node (ref "H8") (pin "3") (pinfunction "3_3") (pintype "unspecified"))
      (node (ref "H8") (pin "4") (pinfunction "4_4") (pintype "unspecified"))
      (node (ref "T8") (pin "3") (pinfunction "3_3") (pintype "unspecified"))
    )
    (net (code "59") (name "Net-(H9-Pad1)") (class "Default")
      (node (ref "H9") (pin "1") (pinfunction "1_1") (pintype "unspecified"))
      (node (ref "SW5") (pin "1") (pinfunction "1_1") (pintype "unspecified"))
    )
    (net (code "60") (name "Net-(H9-Pad2)") (class "Default")
      (node (ref "H9") (pin "2") (pinfunction "2_2") (pintype "unspecified"))
      (node (ref "SW5") (pin "2") (pinfunction "2_2") (pintype "unspecified"))
    )
    (net (code "61") (name "Net-(H9-Pad3)") (class "Default")
      (node (ref "H9") (pin "3") (pinfunction "3_3") (pintype "unspecified"))
      (node (ref "SW5") (pin "3") (pinfunction "3_3") (pintype "unspecified"))
    )
    (net (code "62") (name "Net-(H9-Pad4)") (class "Default")
      (node (ref "H9") (pin "4") (pinfunction "4_4") (pintype "unspecified"))
      (node (ref "SW5") (pin "6") (pinfunction "6_6") (pintype "unspecified"))
    )
    (net (code "63") (name "Net-(H9-Pad5)") (class "Default")
      (node (ref "H9") (pin "5") (pinfunction "5_5") (pintype "unspecified"))
      (node (ref "SW5") (pin "5") (pinfunction "5_5") (pintype "unspecified"))
    )
    (net (code "64") (name "Net-(H9-Pad6)") (class "Default")
      (node (ref "H9") (pin "6") (pinfunction "6_6") (pintype "unspecified"))
      (node (ref "SW5") (pin "4") (pinfunction "4_4") (pintype "unspecified"))
    )
    (net (code "65") (name "Net-(H10-Pad1)") (class "Default")
      (node (ref "H10") (pin "1") (pinfunction "1_1") (pintype "unspecified"))
      (node (ref "SW2") (pin "1") (pinfunction "1_1") (pintype "unspecified"))
    )
    (net (code "66") (name "Net-(H10-Pad2)") (class "Default")
      (node (ref "H10") (pin "2") (pinfunction "2_2") (pintype "unspecified"))
      (node (ref "SW2") (pin "2") (pinfunction "2_2") (pintype "unspecified"))
    )
    (net (code "67") (name "Net-(H10-Pad3)") (class "Default")
      (node (ref "H10") (pin "3") (pinfunction "3_3") (pintype "unspecified"))
      (node (ref "SW2") (pin "3") (pinfunction "3_3") (pintype "unspecified"))
    )
    (net (code "68") (name "Net-(H10-Pad4)") (class "Default")
      (node (ref "H10") (pin "4") (pinfunction "4_4") (pintype "unspecified"))
      (node (ref "SW2") (pin "6") (pinfunction "6_6") (pintype "unspecified"))
    )
    (net (code "69") (name "Net-(H10-Pad5)") (class "Default")
      (node (ref "H10") (pin "5") (pinfunction "5_5") (pintype "unspecified"))
      (node (ref "SW2") (pin "5") (pinfunction "5_5") (pintype "unspecified"))
    )
    (net (code "70") (name "Net-(H10-Pad6)") (class "Default")
      (node (ref "H10") (pin "6") (pinfunction "6_6") (pintype "unspecified"))
      (node (ref "SW2") (pin "4") (pinfunction "4_4") (pintype "unspecified"))
    )
    (net (code "71") (name "Net-(H11-Pad1)") (class "Default")
      (node (ref "H11") (pin "1") (pinfunction "1_1") (pintype "unspecified"))
      (node (ref "SW3") (pin "1") (pinfunction "1_1") (pintype "unspecified"))
    )
    (net (code "72") (name "Net-(H11-Pad2)") (class "Default")
      (node (ref "H11") (pin "2") (pinfunction "2_2") (pintype "unspecified"))
      (node (ref "SW3") (pin "2") (pinfunction "2_2") (pintype "unspecified"))
    )
    (net (code "73") (name "Net-(H11-Pad3)") (class "Default")
      (node (ref "H11") (pin "3") (pinfunction "3_3") (pintype "unspecified"))
      (node (ref "SW3") (pin "3") (pinfunction "3_3") (pintype "unspecified"))
    )
    (net (code "74") (name "Net-(H11-Pad4)") (class "Default")
      (node (ref "H11") (pin "4") (pinfunction "4_4") (pintype "unspecified"))
      (node (ref "SW3") (pin "6") (pinfunction "6_6") (pintype "unspecified"))
    )
    (net (code "75") (name "Net-(H11-Pad5)") (class "Default")
      (node (ref "H11") (pin "5") (pinfunction "5_5") (pintype "unspecified"))
      (node (ref "SW3") (pin "5") (pinfunction "5_5") (pintype "unspecified"))
    )
    (net (code "76") (name "Net-(H11-Pad6)") (class "Default")
      (node (ref "H11") (pin "6") (pinfunction "6_6") (pintype "unspecified"))
      (node (ref "SW3") (pin "4") (pinfunction "4_4") (pintype "unspecified"))
    )
    (net (code "77") (name "Net-(H12-Pad1)") (class "Default")
      (node (ref "H12") (pin "1") (pinfunction "1_1") (pintype "unspecified"))
      (node (ref "SW4") (pin "1") (pinfunction "1_1") (pintype "unspecified"))
    )
    (net (code "78") (name "Net-(H12-Pad2)") (class "Default")
      (node (ref "H12") (pin "2") (pinfunction "2_2") (pintype "unspecified"))
      (node (ref "SW4") (pin "2") (pinfunction "2_2") (pintype "unspecified"))
    )
    (net (code "79") (name "Net-(H12-Pad3)") (class "Default")
      (node (ref "H12") (pin "3") (pinfunction "3_3") (pintype "unspecified"))
      (node (ref "SW4") (pin "3") (pinfunction "3_3") (pintype "unspecified"))
    )
    (net (code "80") (name "Net-(H12-Pad4)") (class "Default")
      (node (ref "H12") (pin "4") (pinfunction "4_4") (pintype "unspecified"))
      (node (ref "SW4") (pin "6") (pinfunction "6_6") (pintype "unspecified"))
    )
    (net (code "81") (name "Net-(H12-Pad5)") (class "Default")
      (node (ref "H12") (pin "5") (pinfunction "5_5") (pintype "unspecified"))
      (node (ref "SW4") (pin "5") (pinfunction "5_5") (pintype "unspecified"))
    )
    (net (code "82") (name "Net-(H12-Pad6)") (class "Default")
      (node (ref "H12") (pin "6") (pinfunction "6_6") (pintype "unspecified"))
      (node (ref "SW4") (pin "4") (pinfunction "4_4") (pintype "unspecified"))
    )
    (net (code "83") (name "Net-(H13-Pad1)") (class "Default")
      (node (ref "H13") (pin "1") (pinfunction "1_1") (pintype "unspecified"))
      (node (ref "SW7") (pin "1") (pinfunction "1_1") (pintype "unspecified"))
    )
    (net (code "84") (name "Net-(H13-Pad2)") (class "Default")
      (node (ref "H13") (pin "2") (pinfunction "2_2") (pintype "unspecified"))
      (node (ref "SW7") (pin "2") (pinfunction "2_2") (pintype "unspecified"))
    )
    (net (code "85") (name "Net-(H13-Pad3)") (class "Default")
      (node (ref "H13") (pin "3") (pinfunction "3_3") (pintype "unspecified"))
      (node (ref "SW7") (pin "3") (pinfunction "3_3") (pintype "unspecified"))
    )
    (net (code "86") (name "Net-(H13-Pad4)") (class "Default")
      (node (ref "H13") (pin "4") (pinfunction "4_4") (pintype "unspecified"))
      (node (ref "SW7") (pin "6") (pinfunction "6_6") (pintype "unspecified"))
    )
    (net (code "87") (name "Net-(H13-Pad5)") (class "Default")
      (node (ref "H13") (pin "5") (pinfunction "5_5") (pintype "unspecified"))
      (node (ref "SW7") (pin "5") (pinfunction "5_5") (pintype "unspecified"))
    )
    (net (code "88") (name "Net-(H13-Pad6)") (class "Default")
      (node (ref "H13") (pin "6") (pinfunction "6_6") (pintype "unspecified"))
      (node (ref "SW7") (pin "4") (pinfunction "4_4") (pintype "unspecified"))
    )
    (net (code "89") (name "Net-(H14-Pad1)") (class "Default")
      (node (ref "H14") (pin "1") (pinfunction "1_1") (pintype "unspecified"))
      (node (ref "SW8") (pin "1") (pinfunction "1_1") (pintype "unspecified"))
    )
    (net (code "90") (name "Net-(H14-Pad2)") (class "Default")
      (node (ref "H14") (pin "2") (pinfunction "2_2") (pintype "unspecified"))
      (node (ref "SW8") (pin "2") (pinfunction "2_2") (pintype "unspecified"))
    )
    (net (code "91") (name "Net-(H14-Pad3)") (class "Default")
      (node (ref "H14") (pin "3") (pinfunction "3_3") (pintype "unspecified"))
      (node (ref "SW8") (pin "3") (pinfunction "3_3") (pintype "unspecified"))
    )
    (net (code "92") (name "Net-(H14-Pad4)") (class "Default")
      (node (ref "H14") (pin "4") (pinfunction "4_4") (pintype "unspecified"))
      (node (ref "SW8") (pin "6") (pinfunction "6_6") (pintype "unspecified"))
    )
    (net (code "93") (name "Net-(H14-Pad5)") (class "Default")
      (node (ref "H14") (pin "5") (pinfunction "5_5") (pintype "unspecified"))
      (node (ref "SW8") (pin "5") (pinfunction "5_5") (pintype "unspecified"))
    )
    (net (code "94") (name "Net-(H14-Pad6)") (class "Default")
      (node (ref "H14") (pin "6") (pinfunction "6_6") (pintype "unspecified"))
      (node (ref "SW8") (pin "4") (pinfunction "4_4") (pintype "unspecified"))
    )
    (net (code "95") (name "Net-(H24-Pad1)") (class "Default")
      (node (ref "H24") (pin "1") (pinfunction "1_1") (pintype "input"))
      (node (ref "H24") (pin "2") (pinfunction "2_2") (pintype "input"))
    )
    (net (code "96") (name "Net-(H24-Pad3)") (class "Default")
      (node (ref "H24") (pin "3") (pinfunction "3_3") (pintype "input"))
      (node (ref "H24") (pin "4") (pinfunction "4_4") (pintype "input"))
    )
    (net (code "97") (name "Net-(H25-Pad1)") (class "Default")
      (node (ref "H25") (pin "1") (pinfunction "1_1") (pintype "input"))
      (node (ref "H25") (pin "2") (pinfunction "2_2") (pintype "input"))
    )
    (net (code "98") (name "Net-(H25-Pad3)") (class "Default")
      (node (ref "H25") (pin "3") (pinfunction "3_3") (pintype "input"))
      (node (ref "H25") (pin "4") (pinfunction "4_4") (pintype "input"))
    )
    (net (code "99") (name "Net-(PD1-K)") (class "Default")
      (node (ref "PC2") (pin "1") (pinfunction "1_1") (pintype "input"))
      (node (ref "PD1") (pin "1") (pinfunction "K_1") (pintype "input"))
      (node (ref "PD2") (pin "2") (pinfunction "A_2") (pintype "input"))
    )
    (net (code "100") (name "Net-(PD5-A)") (class "Default")
      (node (ref "PD5") (pin "2") (pinfunction "A_2") (pintype "input"))
      (node (ref "PR3") (pin "2") (pinfunction "2_2") (pintype "input"))
    )
    (net (code "101") (name "Net-(PD6-A)") (class "Default")
      (node (ref "D-SUB") (pin "5") (pinfunction "5_5") (pintype "unspecified"))
      (node (ref "PD6") (pin "2") (pinfunction "A_2") (pintype "input"))
      (node (ref "PD7") (pin "1") (pinfunction "C_1") (pintype "input"))
    )
    (net (code "102") (name "Net-(PPD1-A)") (class "Default")
      (node (ref "DC1") (pin "2") (pinfunction "2_2") (pintype "input"))
      (node (ref "DC1") (pin "3") (pinfunction "3_3") (pintype "input"))
      (node (ref "PPD1") (pin "2") (pinfunction "A_2") (pintype "input"))
    )
    (net (code "103") (name "Net-(PPD1-K)") (class "Default")
      (node (ref "POWER") (pin "2") (pinfunction "2_2") (pintype "unspecified"))
      (node (ref "PPD1") (pin "1") (pinfunction "K_1") (pintype "input"))
    )
    (net (code "104") (name "Net-(U2-A)") (class "Default")
      (node (ref "D-SUB") (pin "1") (pinfunction "1_1") (pintype "unspecified"))
      (node (ref "U2") (pin "2") (pinfunction "A_2") (pintype "unspecified"))
      (node (ref "U3") (pin "1") (pinfunction "C_1") (pintype "unspecified"))
    )
    (net (code "105") (name "OUT") (class "Default")
      (node (ref "BYPASS") (pin "5") (pinfunction "5_5") (pintype "unspecified"))
      (node (ref "OUT1") (pin "6") (pinfunction "6_6") (pintype "input"))
      (node (ref "OUT1") (pin "7") (pinfunction "7_7") (pintype "input"))
    )
    (net (code "106") (name "PGND") (class "Default")
      (node (ref "CP1") (pin "3") (pinfunction "GND_3") (pintype "unspecified"))
      (node (ref "H15") (pin "2") (pinfunction "2_2") (pintype "unspecified"))
      (node (ref "H16") (pin "2") (pinfunction "2_2") (pintype "unspecified"))
      (node (ref "H17") (pin "2") (pinfunction "2_2") (pintype "unspecified"))
      (node (ref "H18") (pin "2") (pinfunction "2_2") (pintype "unspecified"))
      (node (ref "PF1") (pin "2") (pinfunction "2_2") (pintype "input"))
      (node (ref "PF10") (pin "1") (pinfunction "1_1") (pintype "input"))
      (node (ref "PF11") (pin "2") (pinfunction "2_2") (pintype "input"))
      (node (ref "PF12") (pin "2") (pinfunction "2_2") (pintype "input"))
      (node (ref "PF13") (pin "1") (pinfunction "1_1") (pintype "input"))
      (node (ref "PF2") (pin "1") (pinfunction "1_1") (pintype "input"))
      (node (ref "PF8") (pin "2") (pinfunction "2_2") (pintype "input"))
      (node (ref "PF9") (pin "1") (pinfunction "1_1") (pintype "input"))
      (node (ref "VR1") (pin "2") (pinfunction "GND_2") (pintype "unspecified"))
    )
    (net (code "107") (name "unconnected-(CP1-LV-Pad6)") (class "Default")
      (node (ref "CP1") (pin "6") (pinfunction "LV_6") (pintype "unspecified"))
    )
    (net (code "108") (name "unconnected-(CP1-OBC-Pad7)") (class "Default")
      (node (ref "CP1") (pin "7") (pinfunction "OBC_7") (pintype "unspecified"))
    )
    (net (code "109") (name "unconnected-(D-SUB-Pad6)") (class "Default")
      (node (ref "D-SUB") (pin "6") (pinfunction "6_6") (pintype "unspecified+no_connect"))
    )
    (net (code "110") (name "unconnected-(POWER-Pad3)") (class "Default")
      (node (ref "POWER") (pin "3") (pinfunction "3_3") (pintype "unspecified+no_connect"))
    )
  )
)
